# OBC.net
KiCad netlist of a schematic drawn in EAGLE
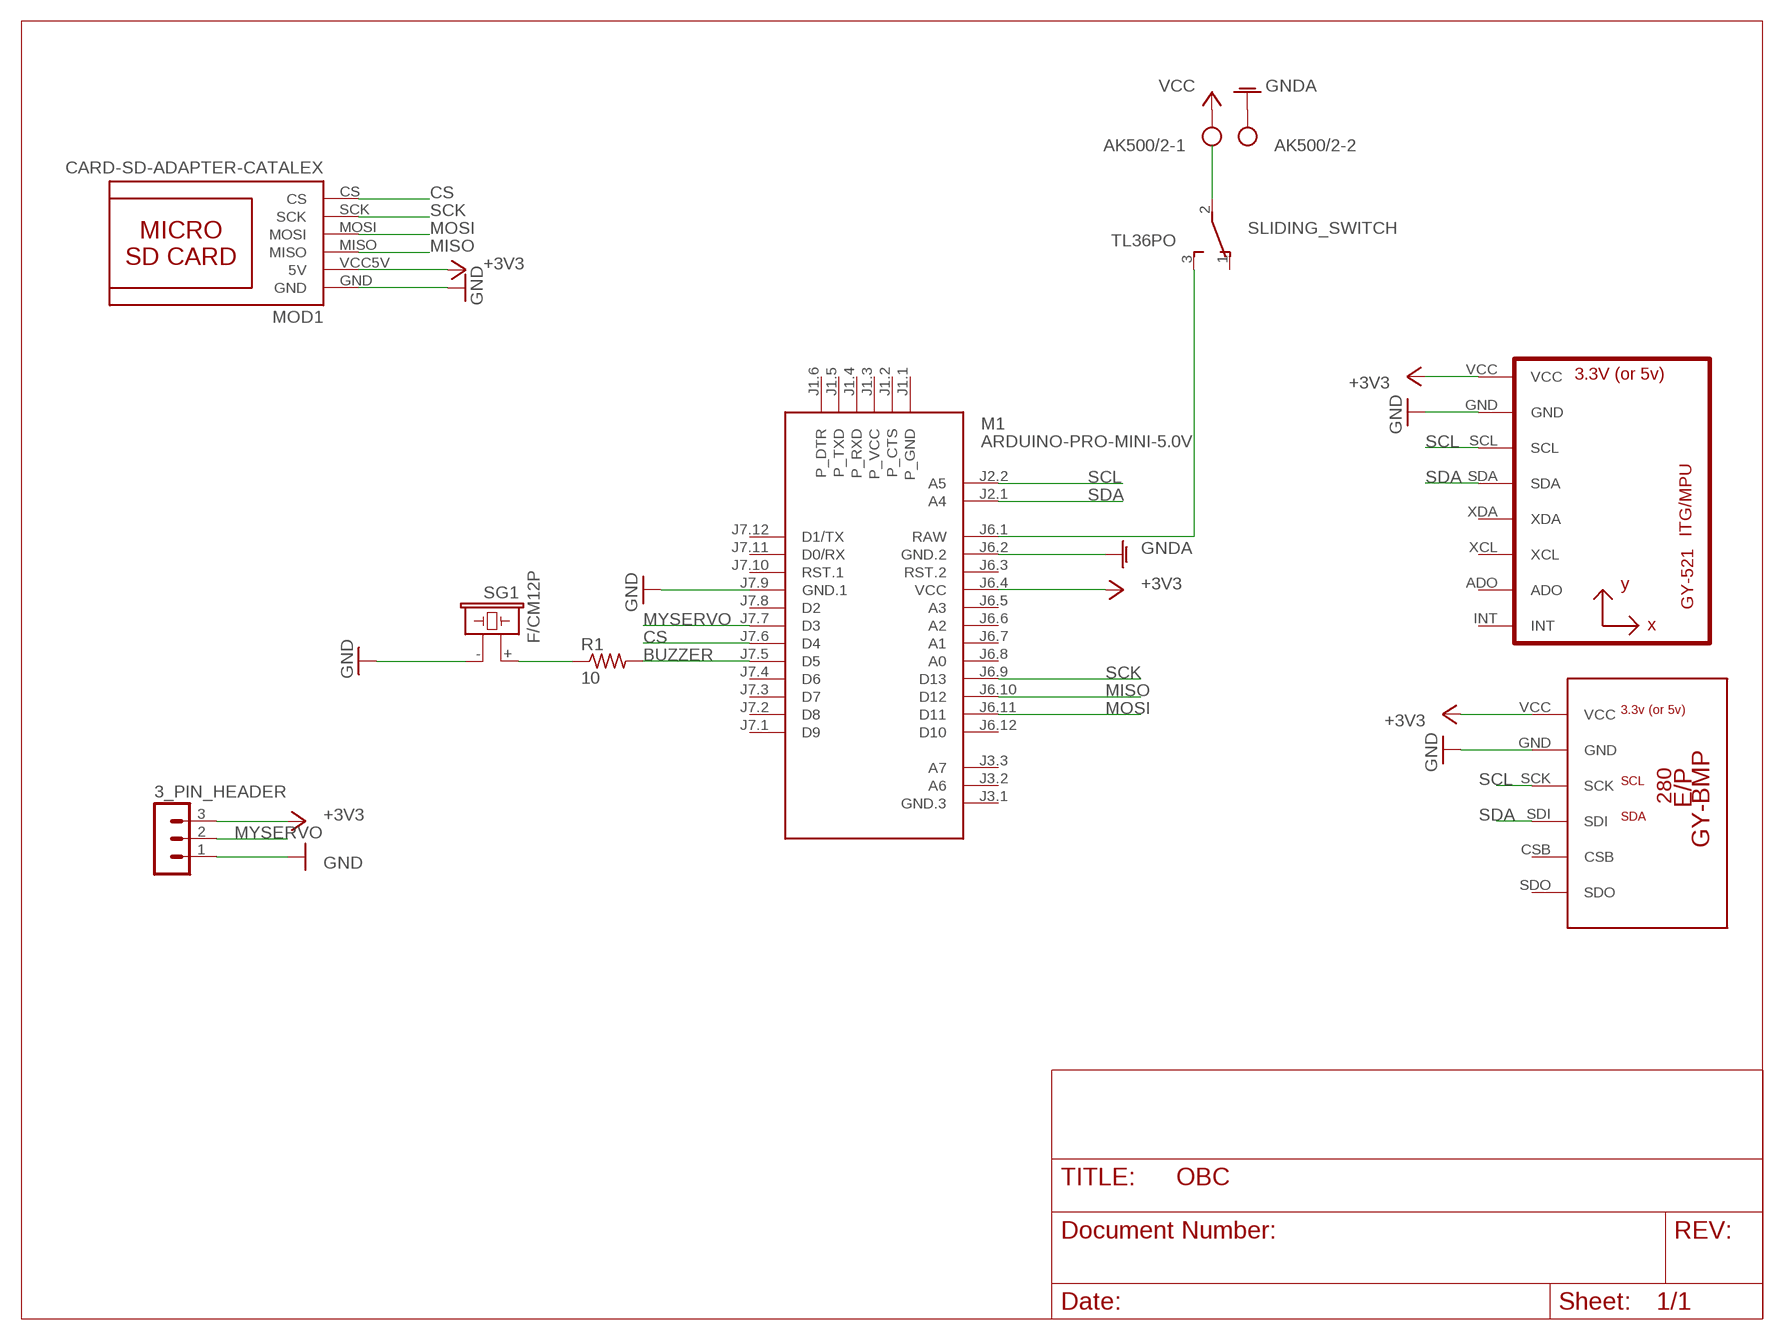
[diagram p0: schematic, sheet 1]

(export (version "E")
  (design (tool "Eeschema 10.0.6"))
  (components
    (comp (ref "3_PIN_HEADER")
      (value "MA03-1")
      (footprint "eagle-import:MA03-1")
      (libsource (lib "eagle-import") (part "MA03-1"))
    )
    (comp (ref "AK500/2")
      (value "AK500/2")
      (footprint "eagle-import:AK500_2")
      (libsource (lib "eagle-import") (part "AK500/2"))
    )
    (comp (ref "M1")
      (value "ARDUINO-PRO-MINI-5.0V")
      (footprint "eagle-import:ARDUINO-PRO-MINI")
      (libsource (lib "eagle-import") (part "ARDUINO-PRO-MINI-5.0V"))
    )
    (comp (ref "MOD1")
      (value "CARD-SD-ADAPTER-CATALEX")
      (footprint "eagle-import:CARD-SD-ADAPTER-CATALEX")
      (libsource (lib "eagle-import") (part "CARD-SD-ADAPTER-CATALEX"))
    )
    (comp (ref "R1")
      (value "10")
      (footprint "eagle-import:0204_7")
      (libsource (lib "eagle-import") (part "R-US_0204/7"))
    )
    (comp (ref "SG1")
      (value "F/CM12P")
      (footprint "eagle-import:F_CM12P")
      (libsource (lib "eagle-import") (part "F/CM12P"))
    )
    (comp (ref "SLIDING_SWITCH")
      (value "TL36PO")
      (footprint "eagle-import:TL3XPO")
      (libsource (lib "eagle-import") (part "TL36PO"))
    )
    (comp (ref "U$1")
      (value "GY-BPM280")
      (footprint "eagle-import:GY-BMP280-FOOTPRINT")
      (libsource (lib "eagle-import") (part "GY-BPM280"))
    )
    (comp (ref "U1")
      (value "GY-521MPU6050")
      (footprint "eagle-import:GY-521")
      (libsource (lib "eagle-import") (part "GY-521MPU6050"))
    )
  )
  (nets
    (net (code "1") (name "+3V3") (class "Default")
      (node (ref "3_PIN_HEADER") (pin "3") (pinfunction "3_3") (pintype "passive"))
      (node (ref "M1") (pin "J6.4") (pinfunction "VCC_J6.4") (pintype "power_in"))
      (node (ref "MOD1") (pin "VCC5V") (pinfunction "5V_VCC5V") (pintype "power_in"))
      (node (ref "U$1") (pin "VCC") (pinfunction "VCC_VCC") (pintype "bidirectional"))
      (node (ref "U1") (pin "VCC") (pinfunction "VCC_VCC") (pintype "bidirectional"))
    )
    (net (code "2") (name "/BUZZER") (class "Default")
      (node (ref "M1") (pin "J7.5") (pinfunction "D5_J7.5") (pintype "bidirectional"))
      (node (ref "R1") (pin "2") (pinfunction "2_2") (pintype "passive"))
    )
    (net (code "3") (name "/CS") (class "Default")
      (node (ref "M1") (pin "J7.6") (pinfunction "D4_J7.6") (pintype "bidirectional"))
      (node (ref "MOD1") (pin "CS") (pinfunction "CS_CS") (pintype "bidirectional"))
    )
    (net (code "4") (name "/MISO") (class "Default")
      (node (ref "M1") (pin "J6.10") (pinfunction "D12_J6.10") (pintype "bidirectional"))
      (node (ref "MOD1") (pin "MISO") (pinfunction "MISO_MISO") (pintype "bidirectional"))
    )
    (net (code "5") (name "/MOSI") (class "Default")
      (node (ref "M1") (pin "J6.11") (pinfunction "D11_J6.11") (pintype "bidirectional"))
      (node (ref "MOD1") (pin "MOSI") (pinfunction "MOSI_MOSI") (pintype "bidirectional"))
    )
    (net (code "6") (name "/MYSERVO") (class "Default")
      (node (ref "3_PIN_HEADER") (pin "2") (pinfunction "2_2") (pintype "passive"))
      (node (ref "M1") (pin "J7.7") (pinfunction "D3_J7.7") (pintype "bidirectional"))
    )
    (net (code "7") (name "/SCK") (class "Default")
      (node (ref "M1") (pin "J6.9") (pinfunction "D13_J6.9") (pintype "bidirectional"))
      (node (ref "MOD1") (pin "SCK") (pinfunction "SCK_SCK") (pintype "bidirectional"))
    )
    (net (code "8") (name "/SCL") (class "Default")
      (node (ref "M1") (pin "J2.2") (pinfunction "A5_J2.2") (pintype "bidirectional"))
      (node (ref "U$1") (pin "SCK") (pinfunction "SCK_SCK") (pintype "bidirectional"))
      (node (ref "U1") (pin "SCL") (pinfunction "SCL_SCL") (pintype "bidirectional"))
    )
    (net (code "9") (name "/SDA") (class "Default")
      (node (ref "M1") (pin "J2.1") (pinfunction "A4_J2.1") (pintype "bidirectional"))
      (node (ref "U$1") (pin "SDI") (pinfunction "SDI_SDI") (pintype "bidirectional"))
      (node (ref "U1") (pin "SDA") (pinfunction "SDA_SDA") (pintype "bidirectional"))
    )
    (net (code "10") (name "GND") (class "Default")
      (node (ref "3_PIN_HEADER") (pin "1") (pinfunction "1_1") (pintype "passive"))
      (node (ref "M1") (pin "J7.9") (pinfunction "GND.1_J7.9") (pintype "power_in"))
      (node (ref "MOD1") (pin "GND") (pinfunction "GND_GND") (pintype "power_in"))
      (node (ref "SG1") (pin "-") (pinfunction "2_-") (pintype "passive"))
      (node (ref "U$1") (pin "GND") (pinfunction "GND_GND") (pintype "bidirectional"))
      (node (ref "U1") (pin "GND") (pinfunction "GND_GND") (pintype "bidirectional"))
    )
    (net (code "11") (name "GNDA") (class "Default")
      (node (ref "AK500/2") (pin "2") (pinfunction "KL_2") (pintype "passive"))
      (node (ref "M1") (pin "J6.2") (pinfunction "GND.2_J6.2") (pintype "power_in"))
    )
    (net (code "12") (name "Net-(M1-RAW)") (class "Default")
      (node (ref "M1") (pin "J6.1") (pinfunction "RAW_J6.1") (pintype "power_in"))
      (node (ref "SLIDING_SWITCH") (pin "3") (pinfunction "S_3") (pintype "passive"))
    )
    (net (code "13") (name "Net-(SG1-1)") (class "Default")
      (node (ref "R1") (pin "1") (pinfunction "1_1") (pintype "passive"))
      (node (ref "SG1") (pin "+") (pinfunction "1_+") (pintype "passive"))
    )
    (net (code "14") (name "VCC") (class "Default")
      (node (ref "AK500/2") (pin "1") (pinfunction "KL_1") (pintype "passive"))
    )
    (net (code "15") (name "unconnected-(M1-A0-PadJ6.8)") (class "Default")
      (node (ref "M1") (pin "J6.8") (pinfunction "A0_J6.8") (pintype "bidirectional"))
    )
    (net (code "16") (name "unconnected-(M1-A1-PadJ6.7)") (class "Default")
      (node (ref "M1") (pin "J6.7") (pinfunction "A1_J6.7") (pintype "bidirectional"))
    )
    (net (code "17") (name "unconnected-(M1-A2-PadJ6.6)") (class "Default")
      (node (ref "M1") (pin "J6.6") (pinfunction "A2_J6.6") (pintype "bidirectional"))
    )
    (net (code "18") (name "unconnected-(M1-A3-PadJ6.5)") (class "Default")
      (node (ref "M1") (pin "J6.5") (pinfunction "A3_J6.5") (pintype "bidirectional"))
    )
    (net (code "19") (name "unconnected-(M1-A6-PadJ3.2)") (class "Default")
      (node (ref "M1") (pin "J3.2") (pinfunction "A6_J3.2") (pintype "bidirectional"))
    )
    (net (code "20") (name "unconnected-(M1-A7-PadJ3.3)") (class "Default")
      (node (ref "M1") (pin "J3.3") (pinfunction "A7_J3.3") (pintype "bidirectional"))
    )
    (net (code "21") (name "unconnected-(M1-D0{slash}RX-PadJ7.11)") (class "Default")
      (node (ref "M1") (pin "J7.11") (pinfunction "D0/RX_J7.11") (pintype "bidirectional"))
    )
    (net (code "22") (name "unconnected-(M1-D1{slash}TX-PadJ7.12)") (class "Default")
      (node (ref "M1") (pin "J7.12") (pinfunction "D1/TX_J7.12") (pintype "bidirectional"))
    )
    (net (code "23") (name "unconnected-(M1-D2-PadJ7.8)") (class "Default")
      (node (ref "M1") (pin "J7.8") (pinfunction "D2_J7.8") (pintype "bidirectional"))
    )
    (net (code "24") (name "unconnected-(M1-D6-PadJ7.4)") (class "Default")
      (node (ref "M1") (pin "J7.4") (pinfunction "D6_J7.4") (pintype "bidirectional"))
    )
    (net (code "25") (name "unconnected-(M1-D7-PadJ7.3)") (class "Default")
      (node (ref "M1") (pin "J7.3") (pinfunction "D7_J7.3") (pintype "bidirectional"))
    )
    (net (code "26") (name "unconnected-(M1-D8-PadJ7.2)") (class "Default")
      (node (ref "M1") (pin "J7.2") (pinfunction "D8_J7.2") (pintype "bidirectional"))
    )
    (net (code "27") (name "unconnected-(M1-D9-PadJ7.1)") (class "Default")
      (node (ref "M1") (pin "J7.1") (pinfunction "D9_J7.1") (pintype "bidirectional"))
    )
    (net (code "28") (name "unconnected-(M1-D10-PadJ6.12)") (class "Default")
      (node (ref "M1") (pin "J6.12") (pinfunction "D10_J6.12") (pintype "bidirectional"))
    )
    (net (code "29") (name "unconnected-(M1-GND.3-PadJ3.1)") (class "Default")
      (node (ref "M1") (pin "J3.1") (pinfunction "GND.3_J3.1") (pintype "bidirectional"))
    )
    (net (code "30") (name "unconnected-(M1-P_CTS-PadJ1.2)") (class "Default")
      (node (ref "M1") (pin "J1.2") (pinfunction "P_CTS_J1.2") (pintype "bidirectional"))
    )
    (net (code "31") (name "unconnected-(M1-P_DTR-PadJ1.6)") (class "Default")
      (node (ref "M1") (pin "J1.6") (pinfunction "P_DTR_J1.6") (pintype "bidirectional"))
    )
    (net (code "32") (name "unconnected-(M1-P_GND-PadJ1.1)") (class "Default")
      (node (ref "M1") (pin "J1.1") (pinfunction "P_GND_J1.1") (pintype "bidirectional"))
    )
    (net (code "33") (name "unconnected-(M1-P_RXD-PadJ1.4)") (class "Default")
      (node (ref "M1") (pin "J1.4") (pinfunction "P_RXD_J1.4") (pintype "bidirectional"))
    )
    (net (code "34") (name "unconnected-(M1-P_TXD-PadJ1.5)") (class "Default")
      (node (ref "M1") (pin "J1.5") (pinfunction "P_TXD_J1.5") (pintype "bidirectional"))
    )
    (net (code "35") (name "unconnected-(M1-P_VCC-PadJ1.3)") (class "Default")
      (node (ref "M1") (pin "J1.3") (pinfunction "P_VCC_J1.3") (pintype "bidirectional"))
    )
    (net (code "36") (name "unconnected-(M1-RST.1-PadJ7.10)") (class "Default")
      (node (ref "M1") (pin "J7.10") (pinfunction "RST.1_J7.10") (pintype "bidirectional"))
    )
    (net (code "37") (name "unconnected-(M1-RST.2-PadJ6.3)") (class "Default")
      (node (ref "M1") (pin "J6.3") (pinfunction "RST.2_J6.3") (pintype "bidirectional"))
    )
    (net (code "38") (name "unconnected-(SLIDING_SWITCH-O-Pad1)") (class "Default")
      (node (ref "SLIDING_SWITCH") (pin "1") (pinfunction "O_1") (pintype "passive"))
    )
    (net (code "39") (name "unconnected-(SLIDING_SWITCH-P-Pad2)") (class "Default")
      (node (ref "SLIDING_SWITCH") (pin "2") (pinfunction "P_2") (pintype "passive"))
    )
    (net (code "40") (name "unconnected-(U$1-PadCSB)") (class "Default")
      (node (ref "U$1") (pin "CSB") (pinfunction "CSB_CSB") (pintype "bidirectional"))
    )
    (net (code "41") (name "unconnected-(U$1-PadSDO)") (class "Default")
      (node (ref "U$1") (pin "SDO") (pinfunction "SDO_SDO") (pintype "bidirectional"))
    )
    (net (code "42") (name "unconnected-(U1-PadADO)") (class "Default")
      (node (ref "U1") (pin "ADO") (pinfunction "ADO_ADO") (pintype "bidirectional"))
    )
    (net (code "43") (name "unconnected-(U1-PadINT)") (class "Default")
      (node (ref "U1") (pin "INT") (pinfunction "INT_INT") (pintype "bidirectional"))
    )
    (net (code "44") (name "unconnected-(U1-PadXCL)") (class "Default")
      (node (ref "U1") (pin "XCL") (pinfunction "XCL_XCL") (pintype "bidirectional"))
    )
    (net (code "45") (name "unconnected-(U1-PadXDA)") (class "Default")
      (node (ref "U1") (pin "XDA") (pinfunction "XDA_XDA") (pintype "bidirectional"))
    )
  )
)
